# Fri3d_2024_Exp0_Keyboard_00.net
KiCad netlist of a schematic drawn in Altium Designer
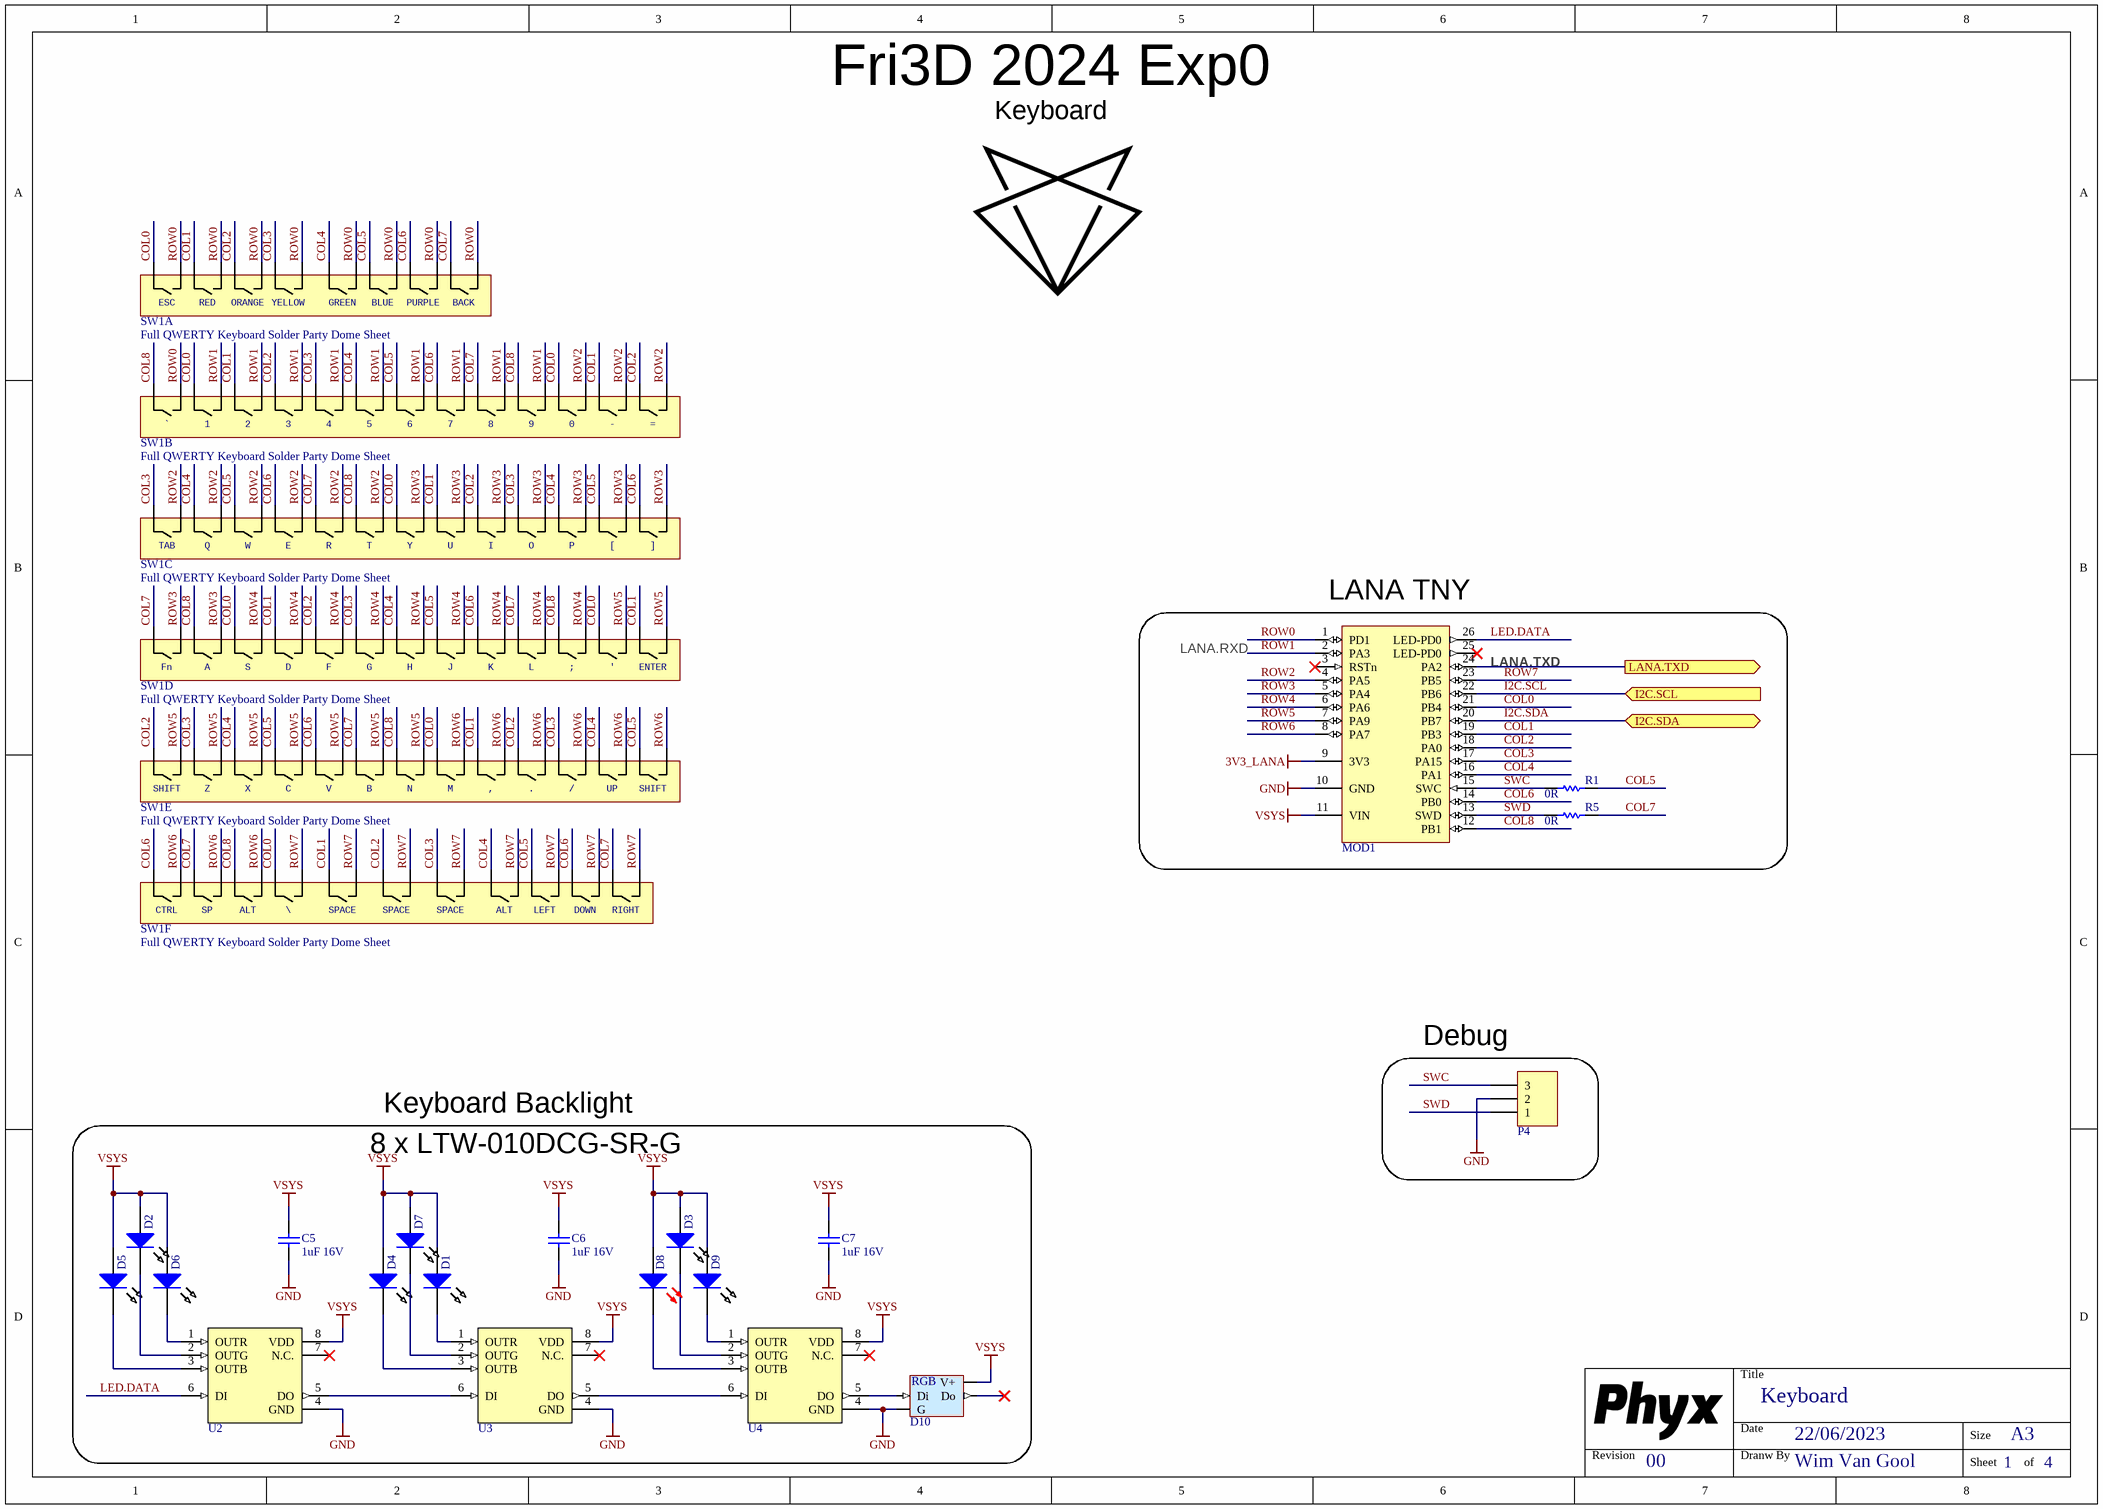
[diagram p0: Fri3d_2024_Exp0_Keyboard_00.SchDoc]

(export (version "E")
  (design (tool "Eeschema 10.0.6"))
  (components
    (comp (ref "C5")
      (value "1uF 16V")
      (footprint "C0603_N")
      (description "Capacitor Ceramic")
      (fields (field (name "Comment") "CAP_CERAMIC"))
      (libsource (lib "Phyx_Components") (part "CAP_CERAMIC"))
    )
    (comp (ref "C6")
      (value "1uF 16V")
      (footprint "C0603_N")
      (description "Capacitor Ceramic")
      (fields (field (name "Comment") "CAP_CERAMIC"))
      (libsource (lib "Phyx_Components") (part "CAP_CERAMIC"))
    )
    (comp (ref "C7")
      (value "1uF 16V")
      (footprint "C0603_N")
      (description "Capacitor Ceramic")
      (fields (field (name "Comment") "CAP_CERAMIC"))
      (libsource (lib "Phyx_Components") (part "CAP_CERAMIC"))
    )
    (comp (ref "D1")
      (value "Side emitting Cool White LED 3.0V 30mA 120° 2900mcd")
      (footprint "LITE_LTW-010DCG")
      (description "=Description")
      (libsource (lib "Phyx_Components") (part "LED_WHITE"))
    )
    (comp (ref "D2")
      (value "Side emitting Cool White LED 3.0V 30mA 120° 2900mcd")
      (footprint "LITE_LTW-010DCG")
      (description "=Description")
      (libsource (lib "Phyx_Components") (part "LED_WHITE"))
    )
    (comp (ref "D3")
      (value "Side emitting Cool White LED 3.0V 30mA 120° 2900mcd")
      (footprint "LITE_LTW-010DCG")
      (description "=Description")
      (libsource (lib "Phyx_Components") (part "LED_WHITE"))
    )
    (comp (ref "D4")
      (value "Side emitting Cool White LED 3.0V 30mA 120° 2900mcd")
      (footprint "LITE_LTW-010DCG")
      (description "=Description")
      (libsource (lib "Phyx_Components") (part "LED_WHITE"))
    )
    (comp (ref "D5")
      (value "Side emitting Cool White LED 3.0V 30mA 120° 2900mcd")
      (footprint "LITE_LTW-010DCG")
      (description "=Description")
      (libsource (lib "Phyx_Components") (part "LED_WHITE"))
    )
    (comp (ref "D6")
      (value "Side emitting Cool White LED 3.0V 30mA 120° 2900mcd")
      (footprint "LITE_LTW-010DCG")
      (description "=Description")
      (libsource (lib "Phyx_Components") (part "LED_WHITE"))
    )
    (comp (ref "D7")
      (value "Side emitting Cool White LED 3.0V 30mA 120° 2900mcd")
      (footprint "LITE_LTW-010DCG")
      (description "=Description")
      (libsource (lib "Phyx_Components") (part "LED_WHITE"))
    )
    (comp (ref "D8")
      (value "Default 0805 Red LED")
      (footprint "LED_0805_RD")
      (description "=Description")
      (libsource (lib "Phyx_Components") (part "LED_RED"))
    )
    (comp (ref "D9")
      (value "Side emitting Cool White LED 3.0V 30mA 120° 2900mcd")
      (footprint "LITE_LTW-010DCG")
      (description "=Description")
      (libsource (lib "Phyx_Components") (part "LED_WHITE"))
    )
    (comp (ref "D10")
      (value "WS2812 based digital RGB LED 5050 Black package")
      (footprint "LED_5050_WS2812B_BLACK")
      (description "=Description")
      (libsource (lib "Phyx_Components") (part "LED_RGB_WS2812B_5050"))
    )
    (comp (ref "MOD1")
      (value "CH23V203 based TNY module")
      (footprint "PHYX_LANA_TNY_SMD")
      (libsource (lib "Phyx_Components") (part "PHYX_LANA_TNY_SMD"))
    )
    (comp (ref "P4")
      (value "Header 3")
      (footprint "HDR1X3")
      (libsource (lib "Phyx_Components") (part "Header 3"))
    )
    (comp (ref "R1")
      (value "0R")
      (footprint "R0603_N")
      (fields (field (name "Comment") "RESISTOR"))
      (libsource (lib "Phyx_Components") (part "RESISTOR"))
    )
    (comp (ref "R5")
      (value "0R")
      (footprint "R0603_N")
      (fields (field (name "Comment") "RESISTOR"))
      (libsource (lib "Phyx_Components") (part "RESISTOR"))
    )
    (comp (ref "SW1")
      (value "Full QWERTY Keyboard Solder Party Dome Sheet")
      (footprint "Solder_Party_Keyb")
      (libsource (lib "CONNECTORS") (part "Solder_Party_Keyb"))
    )
    (comp (ref "U2")
      (value "3 Channel CC LED Driver 20mA")
      (footprint "WS_FSOP-8")
      (description "WS2811F 3-Ch LED Driver")
      (libsource (lib "Phyx_Components") (part "WS_WS2811F"))
    )
    (comp (ref "U3")
      (value "3 Channel CC LED Driver 20mA")
      (footprint "WS_FSOP-8")
      (description "WS2811F 3-Ch LED Driver")
      (libsource (lib "Phyx_Components") (part "WS_WS2811F"))
    )
    (comp (ref "U4")
      (value "3 Channel CC LED Driver 20mA")
      (footprint "WS_FSOP-8")
      (description "WS2811F 3-Ch LED Driver")
      (libsource (lib "Phyx_Components") (part "WS_WS2811F"))
    )
  )
  (nets
    (net (code "2") (name "/COL0") (class "Default")
      (node (ref "MOD1") (pin "21") (pinfunction "PB4_21") (pintype "bidirectional"))
      (node (ref "SW1") (pin "1") (pinfunction "1_1") (pintype "passive"))
      (node (ref "SW1") (pin "109") (pinfunction "109_109") (pintype "passive"))
      (node (ref "SW1") (pin "127") (pinfunction "127_127") (pintype "passive"))
      (node (ref "SW1") (pin "19") (pinfunction "19_19") (pintype "passive"))
      (node (ref "SW1") (pin "37") (pinfunction "37_37") (pintype "passive"))
      (node (ref "SW1") (pin "55") (pinfunction "55_55") (pintype "passive"))
      (node (ref "SW1") (pin "73") (pinfunction "73_73") (pintype "passive"))
      (node (ref "SW1") (pin "91") (pinfunction "91_91") (pintype "passive"))
    )
    (net (code "3") (name "/COL1") (class "Default")
      (node (ref "MOD1") (pin "19") (pinfunction "PB3_19") (pintype "bidirectional"))
      (node (ref "SW1") (pin "111") (pinfunction "111_111") (pintype "passive"))
      (node (ref "SW1") (pin "129") (pinfunction "129_129") (pintype "passive"))
      (node (ref "SW1") (pin "21") (pinfunction "21_21") (pintype "passive"))
      (node (ref "SW1") (pin "3") (pinfunction "3_3") (pintype "passive"))
      (node (ref "SW1") (pin "39") (pinfunction "39_39") (pintype "passive"))
      (node (ref "SW1") (pin "57") (pinfunction "57_57") (pintype "passive"))
      (node (ref "SW1") (pin "75") (pinfunction "75_75") (pintype "passive"))
      (node (ref "SW1") (pin "93") (pinfunction "93_93") (pintype "passive"))
    )
    (net (code "4") (name "/COL2") (class "Default")
      (node (ref "MOD1") (pin "18") (pinfunction "PA0_18") (pintype "bidirectional"))
      (node (ref "SW1") (pin "113") (pinfunction "113_113") (pintype "passive"))
      (node (ref "SW1") (pin "131") (pinfunction "131_131") (pintype "passive"))
      (node (ref "SW1") (pin "23") (pinfunction "23_23") (pintype "passive"))
      (node (ref "SW1") (pin "41") (pinfunction "41_41") (pintype "passive"))
      (node (ref "SW1") (pin "5") (pinfunction "5_5") (pintype "passive"))
      (node (ref "SW1") (pin "59") (pinfunction "59_59") (pintype "passive"))
      (node (ref "SW1") (pin "77") (pinfunction "77_77") (pintype "passive"))
      (node (ref "SW1") (pin "95") (pinfunction "95_95") (pintype "passive"))
    )
    (net (code "5") (name "/COL3") (class "Default")
      (node (ref "MOD1") (pin "17") (pinfunction "PA15_17") (pintype "bidirectional"))
      (node (ref "SW1") (pin "115") (pinfunction "115_115") (pintype "passive"))
      (node (ref "SW1") (pin "133") (pinfunction "133_133") (pintype "passive"))
      (node (ref "SW1") (pin "25") (pinfunction "25_25") (pintype "passive"))
      (node (ref "SW1") (pin "43") (pinfunction "43_43") (pintype "passive"))
      (node (ref "SW1") (pin "61") (pinfunction "61_61") (pintype "passive"))
      (node (ref "SW1") (pin "7") (pinfunction "7_7") (pintype "passive"))
      (node (ref "SW1") (pin "79") (pinfunction "79_79") (pintype "passive"))
      (node (ref "SW1") (pin "97") (pinfunction "97_97") (pintype "passive"))
    )
    (net (code "6") (name "/COL4") (class "Default")
      (node (ref "MOD1") (pin "16") (pinfunction "PA1_16") (pintype "bidirectional"))
      (node (ref "SW1") (pin "117") (pinfunction "117_117") (pintype "passive"))
      (node (ref "SW1") (pin "135") (pinfunction "135_135") (pintype "passive"))
      (node (ref "SW1") (pin "27") (pinfunction "27_27") (pintype "passive"))
      (node (ref "SW1") (pin "45") (pinfunction "45_45") (pintype "passive"))
      (node (ref "SW1") (pin "63") (pinfunction "63_63") (pintype "passive"))
      (node (ref "SW1") (pin "81") (pinfunction "81_81") (pintype "passive"))
      (node (ref "SW1") (pin "9") (pinfunction "9_9") (pintype "passive"))
      (node (ref "SW1") (pin "99") (pinfunction "99_99") (pintype "passive"))
    )
    (net (code "7") (name "/COL5") (class "Default")
      (node (ref "R1") (pin "1") (pinfunction "1_1") (pintype "passive"))
      (node (ref "SW1") (pin "101") (pinfunction "101_101") (pintype "passive"))
      (node (ref "SW1") (pin "11") (pinfunction "11_11") (pintype "passive"))
      (node (ref "SW1") (pin "119") (pinfunction "119_119") (pintype "passive"))
      (node (ref "SW1") (pin "137") (pinfunction "137_137") (pintype "passive"))
      (node (ref "SW1") (pin "29") (pinfunction "29_29") (pintype "passive"))
      (node (ref "SW1") (pin "47") (pinfunction "47_47") (pintype "passive"))
      (node (ref "SW1") (pin "65") (pinfunction "65_65") (pintype "passive"))
      (node (ref "SW1") (pin "83") (pinfunction "83_83") (pintype "passive"))
    )
    (net (code "8") (name "/COL6") (class "Default")
      (node (ref "MOD1") (pin "14") (pinfunction "PB0_14") (pintype "bidirectional"))
      (node (ref "SW1") (pin "103") (pinfunction "103_103") (pintype "passive"))
      (node (ref "SW1") (pin "121") (pinfunction "121_121") (pintype "passive"))
      (node (ref "SW1") (pin "13") (pinfunction "13_13") (pintype "passive"))
      (node (ref "SW1") (pin "139") (pinfunction "139_139") (pintype "passive"))
      (node (ref "SW1") (pin "31") (pinfunction "31_31") (pintype "passive"))
      (node (ref "SW1") (pin "49") (pinfunction "49_49") (pintype "passive"))
      (node (ref "SW1") (pin "67") (pinfunction "67_67") (pintype "passive"))
      (node (ref "SW1") (pin "85") (pinfunction "85_85") (pintype "passive"))
    )
    (net (code "9") (name "/COL7") (class "Default")
      (node (ref "R5") (pin "1") (pinfunction "1_1") (pintype "passive"))
      (node (ref "SW1") (pin "105") (pinfunction "105_105") (pintype "passive"))
      (node (ref "SW1") (pin "123") (pinfunction "123_123") (pintype "passive"))
      (node (ref "SW1") (pin "141") (pinfunction "141_141") (pintype "passive"))
      (node (ref "SW1") (pin "15") (pinfunction "15_15") (pintype "passive"))
      (node (ref "SW1") (pin "33") (pinfunction "33_33") (pintype "passive"))
      (node (ref "SW1") (pin "51") (pinfunction "51_51") (pintype "passive"))
      (node (ref "SW1") (pin "69") (pinfunction "69_69") (pintype "passive"))
      (node (ref "SW1") (pin "87") (pinfunction "87_87") (pintype "passive"))
    )
    (net (code "10") (name "/COL8") (class "Default")
      (node (ref "MOD1") (pin "12") (pinfunction "PB1_12") (pintype "bidirectional"))
      (node (ref "SW1") (pin "107") (pinfunction "107_107") (pintype "passive"))
      (node (ref "SW1") (pin "125") (pinfunction "125_125") (pintype "passive"))
      (node (ref "SW1") (pin "17") (pinfunction "17_17") (pintype "passive"))
      (node (ref "SW1") (pin "35") (pinfunction "35_35") (pintype "passive"))
      (node (ref "SW1") (pin "53") (pinfunction "53_53") (pintype "passive"))
      (node (ref "SW1") (pin "71") (pinfunction "71_71") (pintype "passive"))
      (node (ref "SW1") (pin "89") (pinfunction "89_89") (pintype "passive"))
    )
    (net (code "11") (name "/I2C.SCL") (class "Default")
      (node (ref "MOD1") (pin "22") (pinfunction "PB6_22") (pintype "bidirectional"))
    )
    (net (code "12") (name "/I2C.SDA") (class "Default")
      (node (ref "MOD1") (pin "20") (pinfunction "PB7_20") (pintype "bidirectional"))
    )
    (net (code "13") (name "/LANA.TXD") (class "Default")
      (node (ref "MOD1") (pin "24") (pinfunction "PA2_24") (pintype "bidirectional"))
    )
    (net (code "14") (name "/LED.DATA") (class "Default")
      (node (ref "MOD1") (pin "26") (pinfunction "LED-PD0_26") (pintype "output"))
      (node (ref "U2") (pin "6") (pinfunction "DI_6") (pintype "input"))
    )
    (net (code "15") (name "/ROW0") (class "Default")
      (node (ref "MOD1") (pin "1") (pinfunction "PD1_1") (pintype "bidirectional"))
      (node (ref "SW1") (pin "10") (pinfunction "10_10") (pintype "passive"))
      (node (ref "SW1") (pin "12") (pinfunction "12_12") (pintype "passive"))
      (node (ref "SW1") (pin "14") (pinfunction "14_14") (pintype "passive"))
      (node (ref "SW1") (pin "16") (pinfunction "16_16") (pintype "passive"))
      (node (ref "SW1") (pin "18") (pinfunction "18_18") (pintype "passive"))
      (node (ref "SW1") (pin "2") (pinfunction "2_2") (pintype "passive"))
      (node (ref "SW1") (pin "4") (pinfunction "4_4") (pintype "passive"))
      (node (ref "SW1") (pin "6") (pinfunction "6_6") (pintype "passive"))
      (node (ref "SW1") (pin "8") (pinfunction "8_8") (pintype "passive"))
    )
    (net (code "16") (name "/ROW1") (class "Default")
      (node (ref "MOD1") (pin "2") (pinfunction "PA3_2") (pintype "bidirectional"))
      (node (ref "SW1") (pin "20") (pinfunction "20_20") (pintype "passive"))
      (node (ref "SW1") (pin "22") (pinfunction "22_22") (pintype "passive"))
      (node (ref "SW1") (pin "24") (pinfunction "24_24") (pintype "passive"))
      (node (ref "SW1") (pin "26") (pinfunction "26_26") (pintype "passive"))
      (node (ref "SW1") (pin "28") (pinfunction "28_28") (pintype "passive"))
      (node (ref "SW1") (pin "30") (pinfunction "30_30") (pintype "passive"))
      (node (ref "SW1") (pin "32") (pinfunction "32_32") (pintype "passive"))
      (node (ref "SW1") (pin "34") (pinfunction "34_34") (pintype "passive"))
      (node (ref "SW1") (pin "36") (pinfunction "36_36") (pintype "passive"))
    )
    (net (code "17") (name "/ROW2") (class "Default")
      (node (ref "MOD1") (pin "4") (pinfunction "PA5_4") (pintype "bidirectional"))
      (node (ref "SW1") (pin "38") (pinfunction "38_38") (pintype "passive"))
      (node (ref "SW1") (pin "40") (pinfunction "40_40") (pintype "passive"))
      (node (ref "SW1") (pin "42") (pinfunction "42_42") (pintype "passive"))
      (node (ref "SW1") (pin "44") (pinfunction "44_44") (pintype "passive"))
      (node (ref "SW1") (pin "46") (pinfunction "46_46") (pintype "passive"))
      (node (ref "SW1") (pin "48") (pinfunction "48_48") (pintype "passive"))
      (node (ref "SW1") (pin "50") (pinfunction "50_50") (pintype "passive"))
      (node (ref "SW1") (pin "52") (pinfunction "52_52") (pintype "passive"))
      (node (ref "SW1") (pin "54") (pinfunction "54_54") (pintype "passive"))
    )
    (net (code "18") (name "/ROW3") (class "Default")
      (node (ref "MOD1") (pin "5") (pinfunction "PA4_5") (pintype "bidirectional"))
      (node (ref "SW1") (pin "56") (pinfunction "56_56") (pintype "passive"))
      (node (ref "SW1") (pin "58") (pinfunction "58_58") (pintype "passive"))
      (node (ref "SW1") (pin "60") (pinfunction "60_60") (pintype "passive"))
      (node (ref "SW1") (pin "62") (pinfunction "62_62") (pintype "passive"))
      (node (ref "SW1") (pin "64") (pinfunction "64_64") (pintype "passive"))
      (node (ref "SW1") (pin "66") (pinfunction "66_66") (pintype "passive"))
      (node (ref "SW1") (pin "68") (pinfunction "68_68") (pintype "passive"))
      (node (ref "SW1") (pin "70") (pinfunction "70_70") (pintype "passive"))
      (node (ref "SW1") (pin "72") (pinfunction "72_72") (pintype "passive"))
    )
    (net (code "19") (name "/ROW4") (class "Default")
      (node (ref "MOD1") (pin "6") (pinfunction "PA6_6") (pintype "bidirectional"))
      (node (ref "SW1") (pin "74") (pinfunction "74_74") (pintype "passive"))
      (node (ref "SW1") (pin "76") (pinfunction "76_76") (pintype "passive"))
      (node (ref "SW1") (pin "78") (pinfunction "78_78") (pintype "passive"))
      (node (ref "SW1") (pin "80") (pinfunction "80_80") (pintype "passive"))
      (node (ref "SW1") (pin "82") (pinfunction "82_82") (pintype "passive"))
      (node (ref "SW1") (pin "84") (pinfunction "84_84") (pintype "passive"))
      (node (ref "SW1") (pin "86") (pinfunction "86_86") (pintype "passive"))
      (node (ref "SW1") (pin "88") (pinfunction "88_88") (pintype "passive"))
      (node (ref "SW1") (pin "90") (pinfunction "90_90") (pintype "passive"))
    )
    (net (code "20") (name "/ROW5") (class "Default")
      (node (ref "MOD1") (pin "7") (pinfunction "PA9_7") (pintype "bidirectional"))
      (node (ref "SW1") (pin "100") (pinfunction "100_100") (pintype "passive"))
      (node (ref "SW1") (pin "102") (pinfunction "102_102") (pintype "passive"))
      (node (ref "SW1") (pin "104") (pinfunction "104_104") (pintype "passive"))
      (node (ref "SW1") (pin "106") (pinfunction "106_106") (pintype "passive"))
      (node (ref "SW1") (pin "108") (pinfunction "108_108") (pintype "passive"))
      (node (ref "SW1") (pin "92") (pinfunction "92_92") (pintype "passive"))
      (node (ref "SW1") (pin "94") (pinfunction "94_94") (pintype "passive"))
      (node (ref "SW1") (pin "96") (pinfunction "96_96") (pintype "passive"))
      (node (ref "SW1") (pin "98") (pinfunction "98_98") (pintype "passive"))
    )
    (net (code "21") (name "/ROW6") (class "Default")
      (node (ref "MOD1") (pin "8") (pinfunction "PA7_8") (pintype "bidirectional"))
      (node (ref "SW1") (pin "110") (pinfunction "110_110") (pintype "passive"))
      (node (ref "SW1") (pin "112") (pinfunction "112_112") (pintype "passive"))
      (node (ref "SW1") (pin "114") (pinfunction "114_114") (pintype "passive"))
      (node (ref "SW1") (pin "116") (pinfunction "116_116") (pintype "passive"))
      (node (ref "SW1") (pin "118") (pinfunction "118_118") (pintype "passive"))
      (node (ref "SW1") (pin "120") (pinfunction "120_120") (pintype "passive"))
      (node (ref "SW1") (pin "122") (pinfunction "122_122") (pintype "passive"))
      (node (ref "SW1") (pin "124") (pinfunction "124_124") (pintype "passive"))
      (node (ref "SW1") (pin "126") (pinfunction "126_126") (pintype "passive"))
    )
    (net (code "22") (name "/ROW7") (class "Default")
      (node (ref "MOD1") (pin "23") (pinfunction "PB5_23") (pintype "bidirectional"))
      (node (ref "SW1") (pin "128") (pinfunction "128_128") (pintype "passive"))
      (node (ref "SW1") (pin "130") (pinfunction "130_130") (pintype "passive"))
      (node (ref "SW1") (pin "132") (pinfunction "132_132") (pintype "passive"))
      (node (ref "SW1") (pin "134") (pinfunction "134_134") (pintype "passive"))
      (node (ref "SW1") (pin "136") (pinfunction "136_136") (pintype "passive"))
      (node (ref "SW1") (pin "138") (pinfunction "138_138") (pintype "passive"))
      (node (ref "SW1") (pin "140") (pinfunction "140_140") (pintype "passive"))
      (node (ref "SW1") (pin "142") (pinfunction "142_142") (pintype "passive"))
    )
    (net (code "23") (name "/SWC") (class "Default")
      (node (ref "MOD1") (pin "15") (pinfunction "SWC_15") (pintype "input"))
      (node (ref "P4") (pin "3") (pinfunction "3_3") (pintype "passive"))
      (node (ref "R1") (pin "2") (pinfunction "2_2") (pintype "passive"))
    )
    (net (code "24") (name "/SWD") (class "Default")
      (node (ref "MOD1") (pin "13") (pinfunction "SWD_13") (pintype "bidirectional"))
      (node (ref "P4") (pin "1") (pinfunction "1_1") (pintype "passive"))
      (node (ref "R5") (pin "2") (pinfunction "2_2") (pintype "passive"))
    )
    (net (code "25") (name "3V3_LANA") (class "Default")
      (node (ref "MOD1") (pin "9") (pinfunction "3V3_9") (pintype "power_in"))
    )
    (net (code "26") (name "GND") (class "Default")
      (node (ref "C5") (pin "2") (pinfunction "2_2") (pintype "passive"))
      (node (ref "C6") (pin "2") (pinfunction "2_2") (pintype "passive"))
      (node (ref "C7") (pin "2") (pinfunction "2_2") (pintype "passive"))
      (node (ref "D10") (pin "3") (pinfunction "G_3") (pintype "power_in"))
      (node (ref "MOD1") (pin "10") (pinfunction "GND_10") (pintype "power_in"))
      (node (ref "P4") (pin "2") (pinfunction "2_2") (pintype "passive"))
      (node (ref "U2") (pin "4") (pinfunction "GND_4") (pintype "power_in"))
      (node (ref "U3") (pin "4") (pinfunction "GND_4") (pintype "power_in"))
      (node (ref "U4") (pin "4") (pinfunction "GND_4") (pintype "power_in"))
    )
    (net (code "27") (name "Net-(D1-K)") (class "Default")
      (node (ref "D1") (pin "2") (pinfunction "K_2") (pintype "passive"))
      (node (ref "U3") (pin "1") (pinfunction "OUTR_1") (pintype "input"))
    )
    (net (code "28") (name "Net-(D2-K)") (class "Default")
      (node (ref "D2") (pin "2") (pinfunction "K_2") (pintype "passive"))
      (node (ref "U2") (pin "2") (pinfunction "OUTG_2") (pintype "input"))
    )
    (net (code "29") (name "Net-(D3-K)") (class "Default")
      (node (ref "D3") (pin "2") (pinfunction "K_2") (pintype "passive"))
      (node (ref "U4") (pin "2") (pinfunction "OUTG_2") (pintype "input"))
    )
    (net (code "30") (name "Net-(D4-K)") (class "Default")
      (node (ref "D4") (pin "2") (pinfunction "K_2") (pintype "passive"))
      (node (ref "U3") (pin "3") (pinfunction "OUTB_3") (pintype "input"))
    )
    (net (code "31") (name "Net-(D5-K)") (class "Default")
      (node (ref "D5") (pin "2") (pinfunction "K_2") (pintype "passive"))
      (node (ref "U2") (pin "3") (pinfunction "OUTB_3") (pintype "input"))
    )
    (net (code "32") (name "Net-(D6-K)") (class "Default")
      (node (ref "D6") (pin "2") (pinfunction "K_2") (pintype "passive"))
      (node (ref "U2") (pin "1") (pinfunction "OUTR_1") (pintype "input"))
    )
    (net (code "33") (name "Net-(D7-K)") (class "Default")
      (node (ref "D7") (pin "2") (pinfunction "K_2") (pintype "passive"))
      (node (ref "U3") (pin "2") (pinfunction "OUTG_2") (pintype "input"))
    )
    (net (code "34") (name "Net-(D8-K)") (class "Default")
      (node (ref "D8") (pin "2") (pinfunction "K_2") (pintype "passive"))
      (node (ref "U4") (pin "3") (pinfunction "OUTB_3") (pintype "input"))
    )
    (net (code "35") (name "Net-(D9-K)") (class "Default")
      (node (ref "D9") (pin "2") (pinfunction "K_2") (pintype "passive"))
      (node (ref "U4") (pin "1") (pinfunction "OUTR_1") (pintype "input"))
    )
    (net (code "36") (name "Net-(D10-Di)") (class "Default")
      (node (ref "D10") (pin "4") (pinfunction "Di_4") (pintype "input"))
      (node (ref "U4") (pin "5") (pinfunction "DO_5") (pintype "output"))
    )
    (net (code "37") (name "Net-(U2-DO)") (class "Default")
      (node (ref "U2") (pin "5") (pinfunction "DO_5") (pintype "output"))
      (node (ref "U3") (pin "6") (pinfunction "DI_6") (pintype "input"))
    )
    (net (code "38") (name "Net-(U3-DO)") (class "Default")
      (node (ref "U3") (pin "5") (pinfunction "DO_5") (pintype "output"))
      (node (ref "U4") (pin "6") (pinfunction "DI_6") (pintype "input"))
    )
    (net (code "39") (name "VSYS") (class "Default")
      (node (ref "C5") (pin "1") (pinfunction "1_1") (pintype "passive"))
      (node (ref "C6") (pin "1") (pinfunction "1_1") (pintype "passive"))
      (node (ref "C7") (pin "1") (pinfunction "1_1") (pintype "passive"))
      (node (ref "D1") (pin "1") (pinfunction "A_1") (pintype "passive"))
      (node (ref "D10") (pin "1") (pinfunction "V+_1") (pintype "power_in"))
      (node (ref "D2") (pin "1") (pinfunction "A_1") (pintype "passive"))
      (node (ref "D3") (pin "1") (pinfunction "A_1") (pintype "passive"))
      (node (ref "D4") (pin "1") (pinfunction "A_1") (pintype "passive"))
      (node (ref "D5") (pin "1") (pinfunction "A_1") (pintype "passive"))
      (node (ref "D6") (pin "1") (pinfunction "A_1") (pintype "passive"))
      (node (ref "D7") (pin "1") (pinfunction "A_1") (pintype "passive"))
      (node (ref "D8") (pin "1") (pinfunction "A_1") (pintype "passive"))
      (node (ref "D9") (pin "1") (pinfunction "A_1") (pintype "passive"))
      (node (ref "MOD1") (pin "11") (pinfunction "VIN_11") (pintype "power_in"))
      (node (ref "U2") (pin "8") (pinfunction "VDD_8") (pintype "power_in"))
      (node (ref "U3") (pin "8") (pinfunction "VDD_8") (pintype "power_in"))
      (node (ref "U4") (pin "8") (pinfunction "VDD_8") (pintype "power_in"))
    )
    (net (code "40") (name "unconnected-(D10-Do-Pad2)") (class "Default")
      (node (ref "D10") (pin "2") (pinfunction "Do_2") (pintype "output+no_connect"))
    )
    (net (code "41") (name "unconnected-(MOD1-LED-PD0-Pad25)") (class "Default")
      (node (ref "MOD1") (pin "25") (pinfunction "LED-PD0_25") (pintype "output+no_connect"))
    )
    (net (code "42") (name "unconnected-(MOD1-RSTn-Pad3)") (class "Default")
      (node (ref "MOD1") (pin "3") (pinfunction "RSTn_3") (pintype "input+no_connect"))
    )
    (net (code "43") (name "unconnected-(U2-N.C.-Pad7)") (class "Default")
      (node (ref "U2") (pin "7") (pinfunction "N.C._7") (pintype "passive+no_connect"))
    )
    (net (code "44") (name "unconnected-(U3-N.C.-Pad7)") (class "Default")
      (node (ref "U3") (pin "7") (pinfunction "N.C._7") (pintype "passive+no_connect"))
    )
    (net (code "45") (name "unconnected-(U4-N.C.-Pad7)") (class "Default")
      (node (ref "U4") (pin "7") (pinfunction "N.C._7") (pintype "passive+no_connect"))
    )
  )
)
